# Sheet1.net
KiCad netlist of a schematic drawn in Altium Designer
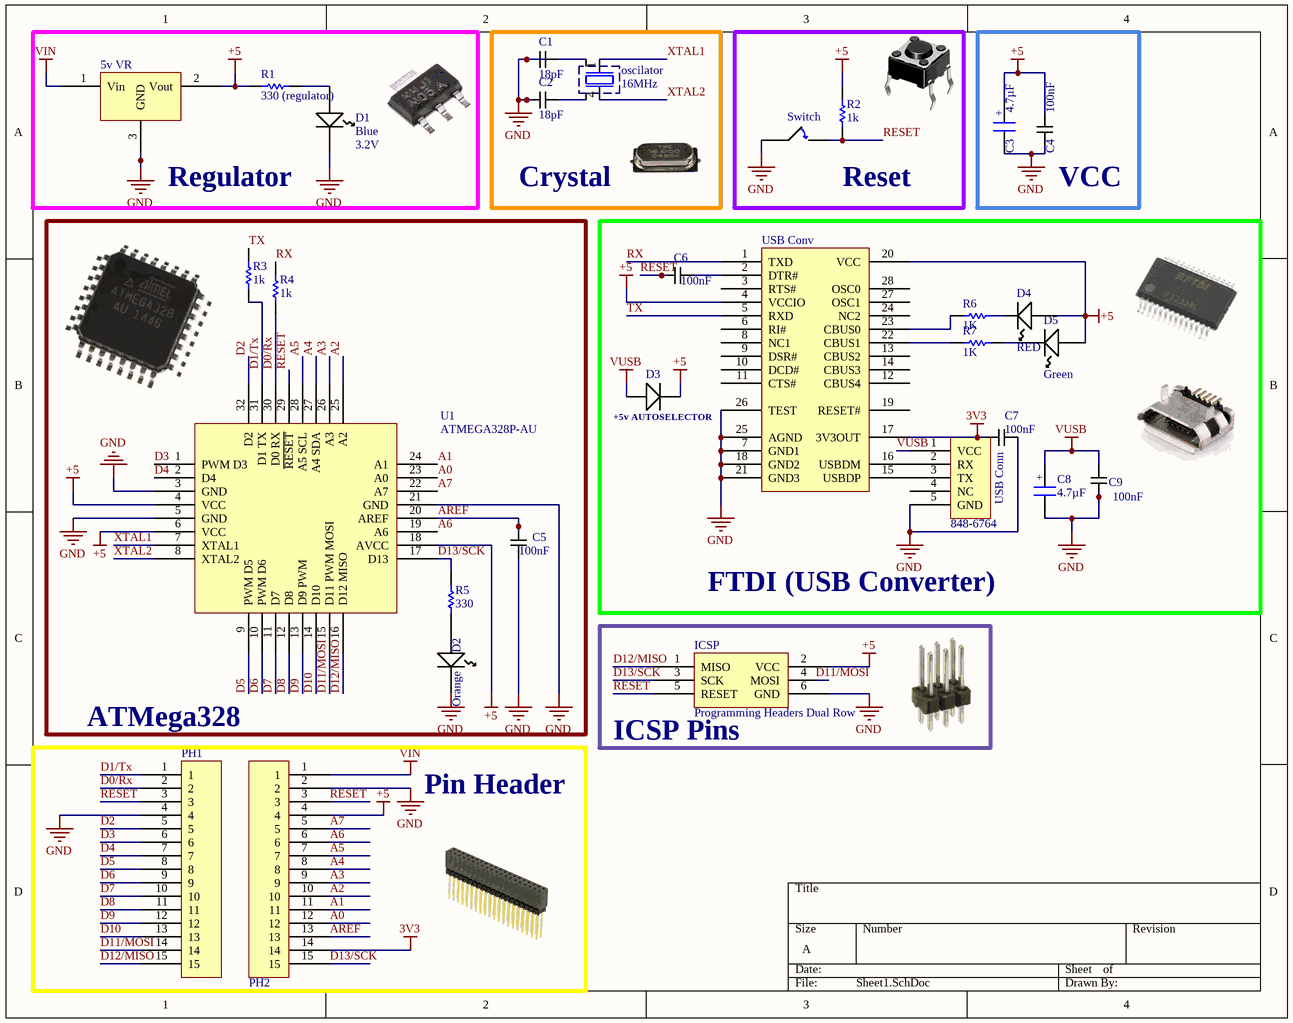
[diagram p0: Sheet1.SchDoc]

(export (version "E")
  (design (tool "Eeschema 10.0.6"))
  (components
    (comp (ref "5v VR")
      (value "LM1117MP-5.0/NOPB, Low Dropout Voltage Regulator, 1.5A, 5 V ±1%, 4-Pin SOT-223")
      (footprint "SOT230P700X180-4N")
      (fields (field (name "MANUFACTURER") "Texas Instruments") (field (name "CREATED BY") "R Kanjee"))
      (libsource (lib "TI Low Dropout Voltage Regulator") (part "LM1117MP-5.0"))
    )
    (comp (ref "C1")
      (value "C0805C180J5GACTU")
      (footprint "CAPCP2012X09N")
      (description "18pF Ceramic Multilayer Capacitor, 50 V dc C0G Dielectric ±5% SMD")
      (fields
        (field (name "MANUFACTURER") "Kemet")
        (field (name "VOLTAGE") "50V")
        (field (name "CAPACITANCE") "18pF")
        (field (name "CREATOR") "Ritesh Kanjee")
      )
      (libsource (lib "RS Components - Capacitors") (part "18pF Ceramic Multilayer Capacitor, 50 V dc C0G Dielectric ±5% SMD"))
    )
    (comp (ref "C2")
      (value "C0805C180J5GACTU")
      (footprint "CAPCP2012X09N")
      (description "18pF Ceramic Multilayer Capacitor, 50 V dc C0G Dielectric ±5% SMD")
      (fields
        (field (name "MANUFACTURER") "Kemet")
        (field (name "VOLTAGE") "50V")
        (field (name "CAPACITANCE") "18pF")
        (field (name "CREATOR") "Ritesh Kanjee")
      )
      (libsource (lib "RS Components - Capacitors") (part "18pF Ceramic Multilayer Capacitor, 50 V dc C0G Dielectric ±5% SMD"))
    )
    (comp (ref "C3")
      (value "4.7µF")
      (footprint "CASE A - 3216X18")
      (description "Capacitor,tantalum,SMT,16V,4.7uF,10%,A-case")
      (fields
        (field (name "TOLERANCE") "10%")
        (field (name "VOLTAGE") "16V")
        (field (name "PUBLISHER") "DPSS")
      )
      (libsource (lib "RS Components - Capacitors") (part "4.7µF Tant RS 496-3545"))
    )
    (comp (ref "C4")
      (value "100nF Ceramic Multilayer Capacitor_1")
      (footprint "CAPCP2012X09N")
      (description "AVX 0805 Standard 100nF Ceramic Multilayer Capacitor, 50 V dc X7R Dielectric ±10% SMD")
      (fields
        (field (name "MANUFACTURER") "AVX")
        (field (name "VOLTAGE") "50V")
        (field (name "CAPACITANCE") "100nF")
        (field (name "CREATOR") "Ritesh Kanjee")
      )
      (libsource (lib "RS Components - Capacitors") (part "100nF Ceramic Multilayer Capacitor_1"))
    )
    (comp (ref "C5")
      (value "100nF Ceramic Multilayer Capacitor_1")
      (footprint "CAPCP2012X09N")
      (description "AVX 0805 Standard 100nF Ceramic Multilayer Capacitor, 50 V dc X7R Dielectric ±10% SMD")
      (fields
        (field (name "MANUFACTURER") "AVX")
        (field (name "VOLTAGE") "50V")
        (field (name "CAPACITANCE") "100nF")
        (field (name "CREATOR") "Ritesh Kanjee")
      )
      (libsource (lib "RS Components - Capacitors") (part "100nF Ceramic Multilayer Capacitor_1"))
    )
    (comp (ref "C6")
      (value "100nF Ceramic Multilayer Capacitor_1")
      (footprint "CAPCP2012X09N")
      (description "AVX 0805 Standard 100nF Ceramic Multilayer Capacitor, 50 V dc X7R Dielectric ±10% SMD")
      (fields
        (field (name "MANUFACTURER") "AVX")
        (field (name "VOLTAGE") "50V")
        (field (name "CAPACITANCE") "100nF")
        (field (name "CREATOR") "Ritesh Kanjee")
      )
      (libsource (lib "RS Components - Capacitors") (part "100nF Ceramic Multilayer Capacitor_1"))
    )
    (comp (ref "C7")
      (value "100nF Ceramic Multilayer Capacitor_1")
      (footprint "CAPCP2012X09N")
      (description "AVX 0805 Standard 100nF Ceramic Multilayer Capacitor, 50 V dc X7R Dielectric ±10% SMD")
      (fields
        (field (name "MANUFACTURER") "AVX")
        (field (name "VOLTAGE") "50V")
        (field (name "CAPACITANCE") "100nF")
        (field (name "CREATOR") "Ritesh Kanjee")
      )
      (libsource (lib "RS Components - Capacitors") (part "100nF Ceramic Multilayer Capacitor_1"))
    )
    (comp (ref "C8")
      (value "4.7µF")
      (footprint "CASE A - 3216X18")
      (description "Capacitor,tantalum,SMT,16V,4.7uF,10%,A-case")
      (fields
        (field (name "TOLERANCE") "10%")
        (field (name "VOLTAGE") "16V")
        (field (name "PUBLISHER") "DPSS")
      )
      (libsource (lib "RS Components - Capacitors") (part "4.7µF Tant RS 496-3545"))
    )
    (comp (ref "C9")
      (value "100nF Ceramic Multilayer Capacitor_1")
      (footprint "CAPCP2012X09N")
      (description "AVX 0805 Standard 100nF Ceramic Multilayer Capacitor, 50 V dc X7R Dielectric ±10% SMD")
      (fields
        (field (name "MANUFACTURER") "AVX")
        (field (name "VOLTAGE") "50V")
        (field (name "CAPACITANCE") "100nF")
        (field (name "CREATOR") "Ritesh Kanjee")
      )
      (libsource (lib "RS Components - Capacitors") (part "100nF Ceramic Multilayer Capacitor_1"))
    )
    (comp (ref "D1")
      (value "(power)Kingbright Blue LED, 60 mcd 120 ° 0805")
      (footprint "LED1913X12NBLUE")
      (description "Kingbright Blue LED, 60 mcd 120 ° 0805")
      (fields
        (field (name "MANUFACTURER") "KingBright")
        (field (name "MANUFACTURER PART NO.") "KP-2012PBC-A")
        (field (name "COLOR") "Blue")
        (field (name "FORWARD VOLTAGE") "3.2V")
        (field (name "CREATOR") "Ritesh Kanjee")
      )
      (libsource (lib "KingBright LEDs") (part "Kingbright Blue LED, 60 mcd 120 ° 0805"))
    )
    (comp (ref "D2")
      (value "(D13 led) Kingbright Orange LED, 200 mcd 120 ° 0805")
      (footprint "LED1913X12NYEL/ORANGE")
      (description "Kingbright Orange LED, 200 mcd 120 ° 0805")
      (fields
        (field (name "MANUFACTURER") "KingBright")
        (field (name "MANUFACTURER PART NO.") "KP-2012SEC")
        (field (name "COLOR") "Orange")
        (field (name "CREATOR") "Ritesh Kanjee")
      )
      (libsource (lib "KingBright LEDs") (part "Kingbright Orange LED, 200 mcd 120 ° 0805"))
    )
    (comp (ref "D3")
      (value "Panasonic DB2J20900L Schottky Diode, 0.5A, 20V, 2.4ns, 2-Pin SMini2 F5 B")
      (footprint "DIOM1712X07N")
      (fields
        (field (name "MANUFACTURER") "Panasonic")
        (field (name "MANUFACTURER PART NO.") "DB2J20900L")
        (field (name "CREATED BY") "R Kanjee")
      )
      (libsource (lib "Panasonic Diodes") (part "Schottky Diode, 0.5A, 20V, 2.4ns, 2-Pin SMini2 F5 B"))
    )
    (comp (ref "D4")
      (value "(TX)Kingbright Red LED, 100 mcd 120 ° 0805")
      (footprint "LED1913X12NRED")
      (description "Kingbright Red LED, 100 mcd 120 ° 0805")
      (fields
        (field (name "MANUFACTURER") "KingBright")
        (field (name "MANUFACTURER PART NO.") "KP-2012SRC-PRV")
        (field (name "COLOR") "RED")
        (field (name "CREATOR") "Ritesh Kanjee")
      )
      (libsource (lib "KingBright LEDs") (part "Kingbright Red LED, 100 mcd 120 ° 0805"))
    )
    (comp (ref "D5")
      (value "(RX)Kingbright Green LED, 70 mcd 120 ° 0805")
      (footprint "LED1913X12NGREEN")
      (description "Kingbright Green LED, 70 mcd 120 ° 0805")
      (fields
        (field (name "MANUFACTURER") "KingBright")
        (field (name "MANUFACTURER PART NO.") "KP-2012MGC")
        (field (name "COLOR") "Green")
        (field (name "CREATOR") "Ritesh Kanjee")
      )
      (libsource (lib "KingBright LEDs") (part "Kingbright Green LED, 70 mcd 120 ° 0805"))
    )
    (comp (ref "ICSP")
      (value "Programming Headers Dual Row")
      (footprint "ISP HEADER")
      (fields
        (field (name "MANUFACTURER") "FCI")
        (field (name "MANUFACTURER PART NO.") "68000-236HLF")
        (field (name "CREATED BY") "R Kanjee")
      )
      (libsource (lib "PCB Headers") (part "Programming ISP, Programming Headers Dual Row"))
    )
    (comp (ref "oscilator")
      (value "16MHz")
      (footprint "Aker S5C Crystal")
      (description "Aker S5C SMT Crystal")
      (fields
        (field (name "MANUFACTURER") "Aker")
        (field (name "MANUFACTURER PART #") "C5S-16.000-12-3030-X")
        (field (name "CREATOR") "R Kanjee")
      )
      (libsource (lib "Aker Crystals") (part "Aker  C5S-16.000-12-3030-X"))
    )
    (comp (ref "PH1")
      (value "connector;str header;single row;.1 cont centers;.095 tail;gold or gtx;36 contact")
      (footprint "Header")
      (fields
        (field (name "MANUFACTURER") "FCI")
        (field (name "MANUFACTURER PART NO.") "68000-236HLF")
        (field (name "CREATED BY") "R Kanjee")
      )
      (libsource (lib "PCB Headers") (part "Single row; PCB headers"))
    )
    (comp (ref "PH2")
      (value "connector;str header;single row;.1 cont centers;.095 tail;gold or gtx;36 contact")
      (footprint "Header")
      (fields
        (field (name "MANUFACTURER") "FCI")
        (field (name "MANUFACTURER PART NO.") "68000-236HLF")
        (field (name "CREATED BY") "R Kanjee")
      )
      (libsource (lib "") (part "Single row; PCB headers_1"))
    )
    (comp (ref "R1")
      (value "330 (regulator)")
      (footprint "RESC1608X55X25NL10T15")
      (description "Chip Resistor, 0 Ohm, +/- 5%, 0.1 W, -55 to 155 degC, 0603 (1608 Metric), RoHS, Tape and Reel")
      (fields (field (name "TOLERANCE") "5%") (field (name "MANUFACTURER") "Yageo"))
      (libsource (lib "Components - resistor - 04.09.24 - 02.15") (part "CMP-2100-03667-1"))
    )
    (comp (ref "R2")
      (value "1k")
      (footprint "RESC1608X55X25NL10T15")
      (description "Chip Resistor, 0 Ohm, +/- 5%, 0.1 W, -55 to 155 degC, 0603 (1608 Metric), RoHS, Tape and Reel")
      (fields (field (name "TOLERANCE") "5%") (field (name "MANUFACTURER") "Yageo"))
      (libsource (lib "Components - resistor - 04.09.24 - 02.15") (part "CMP-2100-03667-1"))
    )
    (comp (ref "R3")
      (value "1k")
      (footprint "RESC1608X55X25NL10T15")
      (description "Chip Resistor, 0 Ohm, +/- 5%, 0.1 W, -55 to 155 degC, 0603 (1608 Metric), RoHS, Tape and Reel")
      (fields (field (name "TOLERANCE") "5%") (field (name "MANUFACTURER") "Yageo"))
      (libsource (lib "Components - resistor - 04.09.24 - 02.15") (part "CMP-2100-03667-1"))
    )
    (comp (ref "R4")
      (value "1k")
      (footprint "RESC1608X55X25NL10T15")
      (description "Chip Resistor, 0 Ohm, +/- 5%, 0.1 W, -55 to 155 degC, 0603 (1608 Metric), RoHS, Tape and Reel")
      (fields (field (name "TOLERANCE") "5%") (field (name "MANUFACTURER") "Yageo"))
      (libsource (lib "Components - resistor - 04.09.24 - 02.15") (part "CMP-2100-03667-1"))
    )
    (comp (ref "R5")
      (value "330")
      (footprint "RESC1608X55X25NL10T15")
      (description "Chip Resistor, 0 Ohm, +/- 5%, 0.1 W, -55 to 155 degC, 0603 (1608 Metric), RoHS, Tape and Reel")
      (fields (field (name "TOLERANCE") "5%") (field (name "MANUFACTURER") "Yageo"))
      (libsource (lib "Components - resistor - 04.09.24 - 02.15") (part "CMP-2100-03667-1"))
    )
    (comp (ref "R6")
      (value "1K")
      (footprint "RESC1608X55X25NL10T15")
      (description "Chip Resistor, 0 Ohm, +/- 5%, 0.1 W, -55 to 155 degC, 0603 (1608 Metric), RoHS, Tape and Reel")
      (fields (field (name "TOLERANCE") "5%") (field (name "MANUFACTURER") "Yageo"))
      (libsource (lib "Components - resistor - 04.09.24 - 02.15") (part "CMP-2100-03667-1"))
    )
    (comp (ref "R7")
      (value "1K")
      (footprint "RESC1608X55X25NL10T15")
      (description "Chip Resistor, 0 Ohm, +/- 5%, 0.1 W, -55 to 155 degC, 0603 (1608 Metric), RoHS, Tape and Reel")
      (fields (field (name "TOLERANCE") "5%") (field (name "MANUFACTURER") "Yageo"))
      (libsource (lib "Components - resistor - 04.09.24 - 02.15") (part "CMP-2100-03667-1"))
    )
    (comp (ref "Switch")
      (value "Button Tactile Switch, NO 0.05 A 0.8mm")
      (footprint "Button8014X17N")
      (fields
        (field (name "MANUFACTURER") "C & K")
        (field (name "MANUFACTURER PART NO.") "B3F1000")
        (field (name "CREATOR") "R Kanjee")
      )
      (libsource (lib "Omron Tactile Switches") (part "Button Tactile Switch, NO 0.05 A 0.8mm"))
    )
    (comp (ref "U1")
      (value "ATMEGA328P-AU")
      (footprint "TQFP80P900X900X120-32N")
      (description "ATMEGA328P-AU, 8 bit AVR Microcontroller 20MHz 1 kB, 32 kB Flash, 2 kB RAM, I2C 32-Pin TQFP")
      (fields (field (name "CREATED BY") "Ritesh Kanjee"))
      (libsource (lib "Atmel Microcontrollers") (part "ATMEGA328P-AU"))
    )
    (comp (ref "USB Conn")
      (value "NewMolex Right Angle SMT Female Type B Micro USB Connector, 30 V ac, 1.8A")
      (footprint "MicroUSB")
      (fields
        (field (name "MANUFACTURER") "Molex")
        (field (name "MANUFACTURER PART NO.") "105017-0001")
        (field (name "RS STOCK NO") "848-6764")
        (field (name "CREATOR") "R Kanjee")
      )
      (libsource (lib "Molex Connectors") (part "Micro USB Connector, 30 V ac, 1.8A"))
    )
    (comp (ref "USB Conv")
      (value "FT232RL, Universal Asynchronous Receiver & Transmitter 3MBd, 28-Pin, SSOP")
      (footprint "SOP65P780X200-28N")
      (fields
        (field (name "MANUFACTURER PART NO.") "FT232RL")
        (field (name "MANUFACTURER") "FTDI Chip")
        (field (name "CREATOR") "R Kanjee")
      )
      (libsource (lib "FTDI RS232toUSB") (part "FT232RL USB to UART, Universal Asynchronous Receiver & Transmitter 3MBd, 28-Pin, SSOP"))
    )
  )
  (nets
    (net (code "1") (name "+5") (class "Default")
      (node (ref "5v VR") (pin "2") (pinfunction "Vout_2") (pintype "passive"))
      (node (ref "C3") (pin "1") (pinfunction "1_1") (pintype "passive"))
      (node (ref "C4") (pin "2") (pinfunction "2_2") (pintype "passive"))
      (node (ref "D3") (pin "1") (pinfunction "1_1") (pintype "passive"))
      (node (ref "D4") (pin "1") (pinfunction "A_1") (pintype "passive"))
      (node (ref "D5") (pin "1") (pinfunction "A_1") (pintype "passive"))
      (node (ref "ICSP") (pin "2") (pinfunction "VCC_2") (pintype "passive"))
      (node (ref "PH2") (pin "4") (pinfunction "4_4") (pintype "passive"))
      (node (ref "R1") (pin "1") (pinfunction "1_1") (pintype "passive"))
      (node (ref "R2") (pin "2") (pinfunction "2_2") (pintype "passive"))
      (node (ref "U1") (pin "18") (pinfunction "AVCC_18") (pintype "passive"))
      (node (ref "U1") (pin "4") (pinfunction "VCC_4") (pintype "passive"))
      (node (ref "U1") (pin "6") (pinfunction "VCC_6") (pintype "passive"))
      (node (ref "USB Conv") (pin "20") (pinfunction "VCC_20") (pintype "passive"))
      (node (ref "USB Conv") (pin "4") (pinfunction "VCCIO_4") (pintype "passive"))
    )
    (net (code "2") (name "/A0") (class "Default")
      (node (ref "PH2") (pin "12") (pinfunction "12_12") (pintype "passive"))
      (node (ref "U1") (pin "23") (pinfunction "A0_23") (pintype "passive"))
    )
    (net (code "3") (name "/A1") (class "Default")
      (node (ref "PH2") (pin "11") (pinfunction "11_11") (pintype "passive"))
      (node (ref "U1") (pin "24") (pinfunction "A1_24") (pintype "passive"))
    )
    (net (code "4") (name "/A2") (class "Default")
      (node (ref "PH2") (pin "10") (pinfunction "10_10") (pintype "passive"))
      (node (ref "U1") (pin "25") (pinfunction "A2_25") (pintype "passive"))
    )
    (net (code "5") (name "/A3") (class "Default")
      (node (ref "PH2") (pin "9") (pinfunction "9_9") (pintype "passive"))
      (node (ref "U1") (pin "26") (pinfunction "A3_26") (pintype "passive"))
    )
    (net (code "6") (name "/A4") (class "Default")
      (node (ref "PH2") (pin "8") (pinfunction "8_8") (pintype "passive"))
      (node (ref "U1") (pin "27") (pinfunction "A4_SDA_27") (pintype "passive"))
    )
    (net (code "7") (name "/A5") (class "Default")
      (node (ref "PH2") (pin "7") (pinfunction "7_7") (pintype "passive"))
      (node (ref "U1") (pin "28") (pinfunction "A5_SCL_28") (pintype "passive"))
    )
    (net (code "8") (name "/A6") (class "Default")
      (node (ref "PH2") (pin "6") (pinfunction "6_6") (pintype "passive"))
      (node (ref "U1") (pin "19") (pinfunction "A6_19") (pintype "passive"))
    )
    (net (code "9") (name "/A7") (class "Default")
      (node (ref "PH2") (pin "5") (pinfunction "5_5") (pintype "passive"))
      (node (ref "U1") (pin "22") (pinfunction "A7_22") (pintype "passive"))
    )
    (net (code "10") (name "/AREF") (class "Default")
      (node (ref "C5") (pin "1") (pinfunction "1_1") (pintype "passive"))
      (node (ref "PH2") (pin "13") (pinfunction "13_13") (pintype "passive"))
      (node (ref "U1") (pin "20") (pinfunction "AREF_20") (pintype "passive"))
    )
    (net (code "11") (name "/D0{slash}Rx") (class "Default")
      (node (ref "PH1") (pin "2") (pinfunction "2_2") (pintype "passive"))
      (node (ref "R4") (pin "1") (pinfunction "1_1") (pintype "passive"))
      (node (ref "U1") (pin "30") (pinfunction "D0_RX_30") (pintype "passive"))
    )
    (net (code "12") (name "/D1{slash}Tx") (class "Default")
      (node (ref "PH1") (pin "1") (pinfunction "1_1") (pintype "passive"))
      (node (ref "R3") (pin "1") (pinfunction "1_1") (pintype "passive"))
      (node (ref "U1") (pin "31") (pinfunction "D1_TX_31") (pintype "passive"))
    )
    (net (code "13") (name "/D2") (class "Default")
      (node (ref "PH1") (pin "5") (pinfunction "5_5") (pintype "passive"))
      (node (ref "U1") (pin "32") (pinfunction "D2_32") (pintype "passive"))
    )
    (net (code "14") (name "/D3") (class "Default")
      (node (ref "PH1") (pin "6") (pinfunction "6_6") (pintype "passive"))
      (node (ref "U1") (pin "1") (pinfunction "PWM_D3_1") (pintype "passive"))
    )
    (net (code "15") (name "/D4") (class "Default")
      (node (ref "PH1") (pin "7") (pinfunction "7_7") (pintype "passive"))
      (node (ref "U1") (pin "2") (pinfunction "D4_2") (pintype "passive"))
    )
    (net (code "16") (name "/D5") (class "Default")
      (node (ref "PH1") (pin "8") (pinfunction "8_8") (pintype "passive"))
      (node (ref "U1") (pin "9") (pinfunction "PWM_D5_9") (pintype "passive"))
    )
    (net (code "17") (name "/D6") (class "Default")
      (node (ref "PH1") (pin "9") (pinfunction "9_9") (pintype "passive"))
      (node (ref "U1") (pin "10") (pinfunction "PWM_D6_10") (pintype "passive"))
    )
    (net (code "18") (name "/D7") (class "Default")
      (node (ref "PH1") (pin "10") (pinfunction "10_10") (pintype "passive"))
      (node (ref "U1") (pin "11") (pinfunction "D7_11") (pintype "passive"))
    )
    (net (code "19") (name "/D8") (class "Default")
      (node (ref "PH1") (pin "11") (pinfunction "11_11") (pintype "passive"))
      (node (ref "U1") (pin "12") (pinfunction "D8_12") (pintype "passive"))
    )
    (net (code "20") (name "/D9") (class "Default")
      (node (ref "PH1") (pin "12") (pinfunction "12_12") (pintype "passive"))
      (node (ref "U1") (pin "13") (pinfunction "D9_PWM_13") (pintype "passive"))
    )
    (net (code "21") (name "/D10") (class "Default")
      (node (ref "PH1") (pin "13") (pinfunction "13_13") (pintype "passive"))
      (node (ref "U1") (pin "14") (pinfunction "D10_14") (pintype "passive"))
    )
    (net (code "22") (name "/D11{slash}MOSI") (class "Default")
      (node (ref "ICSP") (pin "4") (pinfunction "MOSI_4") (pintype "passive"))
      (node (ref "PH1") (pin "14") (pinfunction "14_14") (pintype "passive"))
      (node (ref "U1") (pin "15") (pinfunction "D11_PWM_MOSI_15") (pintype "passive"))
    )
    (net (code "23") (name "/D12{slash}MISO") (class "Default")
      (node (ref "ICSP") (pin "1") (pinfunction "MISO_1") (pintype "passive"))
      (node (ref "PH1") (pin "15") (pinfunction "15_15") (pintype "passive"))
      (node (ref "U1") (pin "16") (pinfunction "D12_MISO_16") (pintype "passive"))
    )
    (net (code "24") (name "/D13{slash}SCK") (class "Default")
      (node (ref "ICSP") (pin "3") (pinfunction "SCK_3") (pintype "passive"))
      (node (ref "PH2") (pin "15") (pinfunction "15_15") (pintype "passive"))
      (node (ref "R5") (pin "2") (pinfunction "2_2") (pintype "passive"))
      (node (ref "U1") (pin "17") (pinfunction "D13_17") (pintype "passive"))
    )
    (net (code "25") (name "/RESET") (class "Default")
      (node (ref "C6") (pin "1") (pinfunction "1_1") (pintype "passive"))
      (node (ref "ICSP") (pin "5") (pinfunction "RESET_5") (pintype "passive"))
      (node (ref "PH1") (pin "3") (pinfunction "3_3") (pintype "passive"))
      (node (ref "PH2") (pin "3") (pinfunction "3_3") (pintype "passive"))
      (node (ref "R2") (pin "1") (pinfunction "1_1") (pintype "passive"))
      (node (ref "Switch") (pin "1") (pinfunction "1_1") (pintype "passive"))
      (node (ref "U1") (pin "29") (pinfunction "~{RESET}_29") (pintype "passive"))
    )
    (net (code "26") (name "/RX") (class "Default")
      (node (ref "R4") (pin "2") (pinfunction "2_2") (pintype "passive"))
      (node (ref "USB Conv") (pin "1") (pinfunction "TXD_1") (pintype "passive"))
    )
    (net (code "27") (name "/TX") (class "Default")
      (node (ref "R3") (pin "2") (pinfunction "2_2") (pintype "passive"))
      (node (ref "USB Conv") (pin "5") (pinfunction "RXD_5") (pintype "passive"))
    )
    (net (code "28") (name "/XTAL1") (class "Default")
      (node (ref "U1") (pin "7") (pinfunction "XTAL1_7") (pintype "passive"))
      (node (ref "oscilator") (pin "1") (pinfunction "1_1") (pintype "passive"))
    )
    (net (code "29") (name "/XTAL2") (class "Default")
      (node (ref "U1") (pin "8") (pinfunction "XTAL2_8") (pintype "passive"))
      (node (ref "oscilator") (pin "4") (pinfunction "4_4") (pintype "passive"))
    )
    (net (code "30") (name "3V3") (class "Default")
      (node (ref "C7") (pin "1") (pinfunction "1_1") (pintype "passive"))
      (node (ref "PH2") (pin "14") (pinfunction "14_14") (pintype "passive"))
      (node (ref "USB Conv") (pin "17") (pinfunction "3V3OUT_17") (pintype "passive"))
    )
    (net (code "31") (name "GND") (class "Default")
      (node (ref "5v VR") (pin "3") (pinfunction "GND_3") (pintype "passive"))
      (node (ref "C1") (pin "1") (pinfunction "1_1") (pintype "passive"))
      (node (ref "C2") (pin "1") (pinfunction "1_1") (pintype "passive"))
      (node (ref "C3") (pin "2") (pinfunction "2_2") (pintype "passive"))
      (node (ref "C4") (pin "1") (pinfunction "1_1") (pintype "passive"))
      (node (ref "C5") (pin "2") (pinfunction "2_2") (pintype "passive"))
      (node (ref "C7") (pin "2") (pinfunction "2_2") (pintype "passive"))
      (node (ref "C8") (pin "2") (pinfunction "2_2") (pintype "passive"))
      (node (ref "C9") (pin "1") (pinfunction "1_1") (pintype "passive"))
      (node (ref "D1") (pin "2") (pinfunction "K_2") (pintype "passive"))
      (node (ref "D2") (pin "2") (pinfunction "K_2") (pintype "passive"))
      (node (ref "ICSP") (pin "6") (pinfunction "GND_6") (pintype "passive"))
      (node (ref "PH1") (pin "4") (pinfunction "4_4") (pintype "passive"))
      (node (ref "PH2") (pin "2") (pinfunction "2_2") (pintype "passive"))
      (node (ref "Switch") (pin "2") (pinfunction "2_2") (pintype "passive"))
      (node (ref "U1") (pin "21") (pinfunction "GND_21") (pintype "passive"))
      (node (ref "U1") (pin "3") (pinfunction "GND_3") (pintype "passive"))
      (node (ref "U1") (pin "5") (pinfunction "GND_5") (pintype "passive"))
      (node (ref "USB Conn") (pin "5") (pinfunction "GND_5") (pintype "passive"))
      (node (ref "USB Conv") (pin "18") (pinfunction "GND2_18") (pintype "passive"))
      (node (ref "USB Conv") (pin "21") (pinfunction "GND3_21") (pintype "passive"))
      (node (ref "USB Conv") (pin "25") (pinfunction "AGND_25") (pintype "passive"))
      (node (ref "USB Conv") (pin "26") (pinfunction "TEST_26") (pintype "passive"))
      (node (ref "USB Conv") (pin "7") (pinfunction "GND1_7") (pintype "passive"))
    )
    (net (code "32") (name "Net-(C1-Pad2)") (class "Default")
      (node (ref "C1") (pin "2") (pinfunction "2_2") (pintype "passive"))
      (node (ref "oscilator") (pin "3") (pinfunction "Gnd_3") (pintype "power_in"))
    )
    (net (code "33") (name "Net-(C2-Pad2)") (class "Default")
      (node (ref "C2") (pin "2") (pinfunction "2_2") (pintype "passive"))
      (node (ref "oscilator") (pin "2") (pinfunction "Gnd_2") (pintype "power_in"))
    )
    (net (code "34") (name "Net-(D1-A)") (class "Default")
      (node (ref "D1") (pin "1") (pinfunction "A_1") (pintype "passive"))
      (node (ref "R1") (pin "2") (pinfunction "2_2") (pintype "passive"))
    )
    (net (code "35") (name "Net-(D2-A)") (class "Default")
      (node (ref "D2") (pin "1") (pinfunction "A_1") (pintype "passive"))
      (node (ref "R5") (pin "1") (pinfunction "1_1") (pintype "passive"))
    )
    (net (code "36") (name "Net-(D4-K)") (class "Default")
      (node (ref "D4") (pin "2") (pinfunction "K_2") (pintype "passive"))
      (node (ref "R6") (pin "1") (pinfunction "1_1") (pintype "passive"))
    )
    (net (code "37") (name "Net-(D5-K)") (class "Default")
      (node (ref "D5") (pin "2") (pinfunction "K_2") (pintype "passive"))
      (node (ref "R7") (pin "1") (pinfunction "1_1") (pintype "passive"))
    )
    (net (code "38") (name "Net-(USB Conn-RX)") (class "Default")
      (node (ref "USB Conn") (pin "2") (pinfunction "RX_2") (pintype "passive"))
      (node (ref "USB Conv") (pin "16") (pinfunction "USBDM_16") (pintype "passive"))
    )
    (net (code "39") (name "Net-(USB Conn-TX)") (class "Default")
      (node (ref "USB Conn") (pin "3") (pinfunction "TX_3") (pintype "passive"))
      (node (ref "USB Conv") (pin "15") (pinfunction "USBDP_15") (pintype "passive"))
    )
    (net (code "40") (name "Net-(USB Conv-CBUS0)") (class "Default")
      (node (ref "R6") (pin "2") (pinfunction "2_2") (pintype "passive"))
      (node (ref "USB Conv") (pin "23") (pinfunction "CBUS0_23") (pintype "passive"))
    )
    (net (code "41") (name "Net-(USB Conv-CBUS1)") (class "Default")
      (node (ref "R7") (pin "2") (pinfunction "2_2") (pintype "passive"))
      (node (ref "USB Conv") (pin "22") (pinfunction "CBUS1_22") (pintype "passive"))
    )
    (net (code "42") (name "Net-(USB Conv-DTR#)") (class "Default")
      (node (ref "C6") (pin "2") (pinfunction "2_2") (pintype "passive"))
      (node (ref "USB Conv") (pin "2") (pinfunction "DTR#_2") (pintype "passive"))
    )
    (net (code "43") (name "VIN") (class "Default")
      (node (ref "5v VR") (pin "1") (pinfunction "Vin_1") (pintype "passive"))
      (node (ref "PH2") (pin "1") (pinfunction "1_1") (pintype "passive"))
    )
    (net (code "44") (name "VUSB") (class "Default")
      (node (ref "C8") (pin "1") (pinfunction "1_1") (pintype "passive"))
      (node (ref "C9") (pin "2") (pinfunction "2_2") (pintype "passive"))
      (node (ref "D3") (pin "2") (pinfunction "2_2") (pintype "passive"))
      (node (ref "USB Conn") (pin "1") (pinfunction "VCC_1") (pintype "passive"))
    )
    (net (code "45") (name "unconnected-(USB Conn-NC-Pad4)") (class "Default")
      (node (ref "USB Conn") (pin "4") (pinfunction "NC_4") (pintype "passive"))
    )
    (net (code "46") (name "unconnected-(USB Conv-CBUS2-Pad13)") (class "Default")
      (node (ref "USB Conv") (pin "13") (pinfunction "CBUS2_13") (pintype "passive"))
    )
    (net (code "47") (name "unconnected-(USB Conv-CBUS3-Pad14)") (class "Default")
      (node (ref "USB Conv") (pin "14") (pinfunction "CBUS3_14") (pintype "passive"))
    )
    (net (code "48") (name "unconnected-(USB Conv-CBUS4-Pad12)") (class "Default")
      (node (ref "USB Conv") (pin "12") (pinfunction "CBUS4_12") (pintype "passive"))
    )
    (net (code "49") (name "unconnected-(USB Conv-CTS#-Pad11)") (class "Default")
      (node (ref "USB Conv") (pin "11") (pinfunction "CTS#_11") (pintype "passive"))
    )
    (net (code "50") (name "unconnected-(USB Conv-DCD#-Pad10)") (class "Default")
      (node (ref "USB Conv") (pin "10") (pinfunction "DCD#_10") (pintype "passive"))
    )
    (net (code "51") (name "unconnected-(USB Conv-DSR#-Pad9)") (class "Default")
      (node (ref "USB Conv") (pin "9") (pinfunction "DSR#_9") (pintype "passive"))
    )
    (net (code "52") (name "unconnected-(USB Conv-NC1-Pad8)") (class "Default")
      (node (ref "USB Conv") (pin "8") (pinfunction "NC1_8") (pintype "passive"))
    )
    (net (code "53") (name "unconnected-(USB Conv-NC2-Pad24)") (class "Default")
      (node (ref "USB Conv") (pin "24") (pinfunction "NC2_24") (pintype "passive"))
    )
    (net (code "54") (name "unconnected-(USB Conv-OSC0-Pad28)") (class "Default")
      (node (ref "USB Conv") (pin "28") (pinfunction "OSC0_28") (pintype "passive"))
    )
    (net (code "55") (name "unconnected-(USB Conv-OSC1-Pad27)") (class "Default")
      (node (ref "USB Conv") (pin "27") (pinfunction "OSC1_27") (pintype "passive"))
    )
    (net (code "56") (name "unconnected-(USB Conv-RESET#-Pad19)") (class "Default")
      (node (ref "USB Conv") (pin "19") (pinfunction "RESET#_19") (pintype "passive"))
    )
    (net (code "57") (name "unconnected-(USB Conv-RI#-Pad6)") (class "Default")
      (node (ref "USB Conv") (pin "6") (pinfunction "RI#_6") (pintype "passive"))
    )
    (net (code "58") (name "unconnected-(USB Conv-RTS#-Pad3)") (class "Default")
      (node (ref "USB Conv") (pin "3") (pinfunction "RTS#_3") (pintype "passive"))
    )
  )
)
